# 3_-_Fuses.net
KiCad netlist of a schematic drawn in Altium Designer
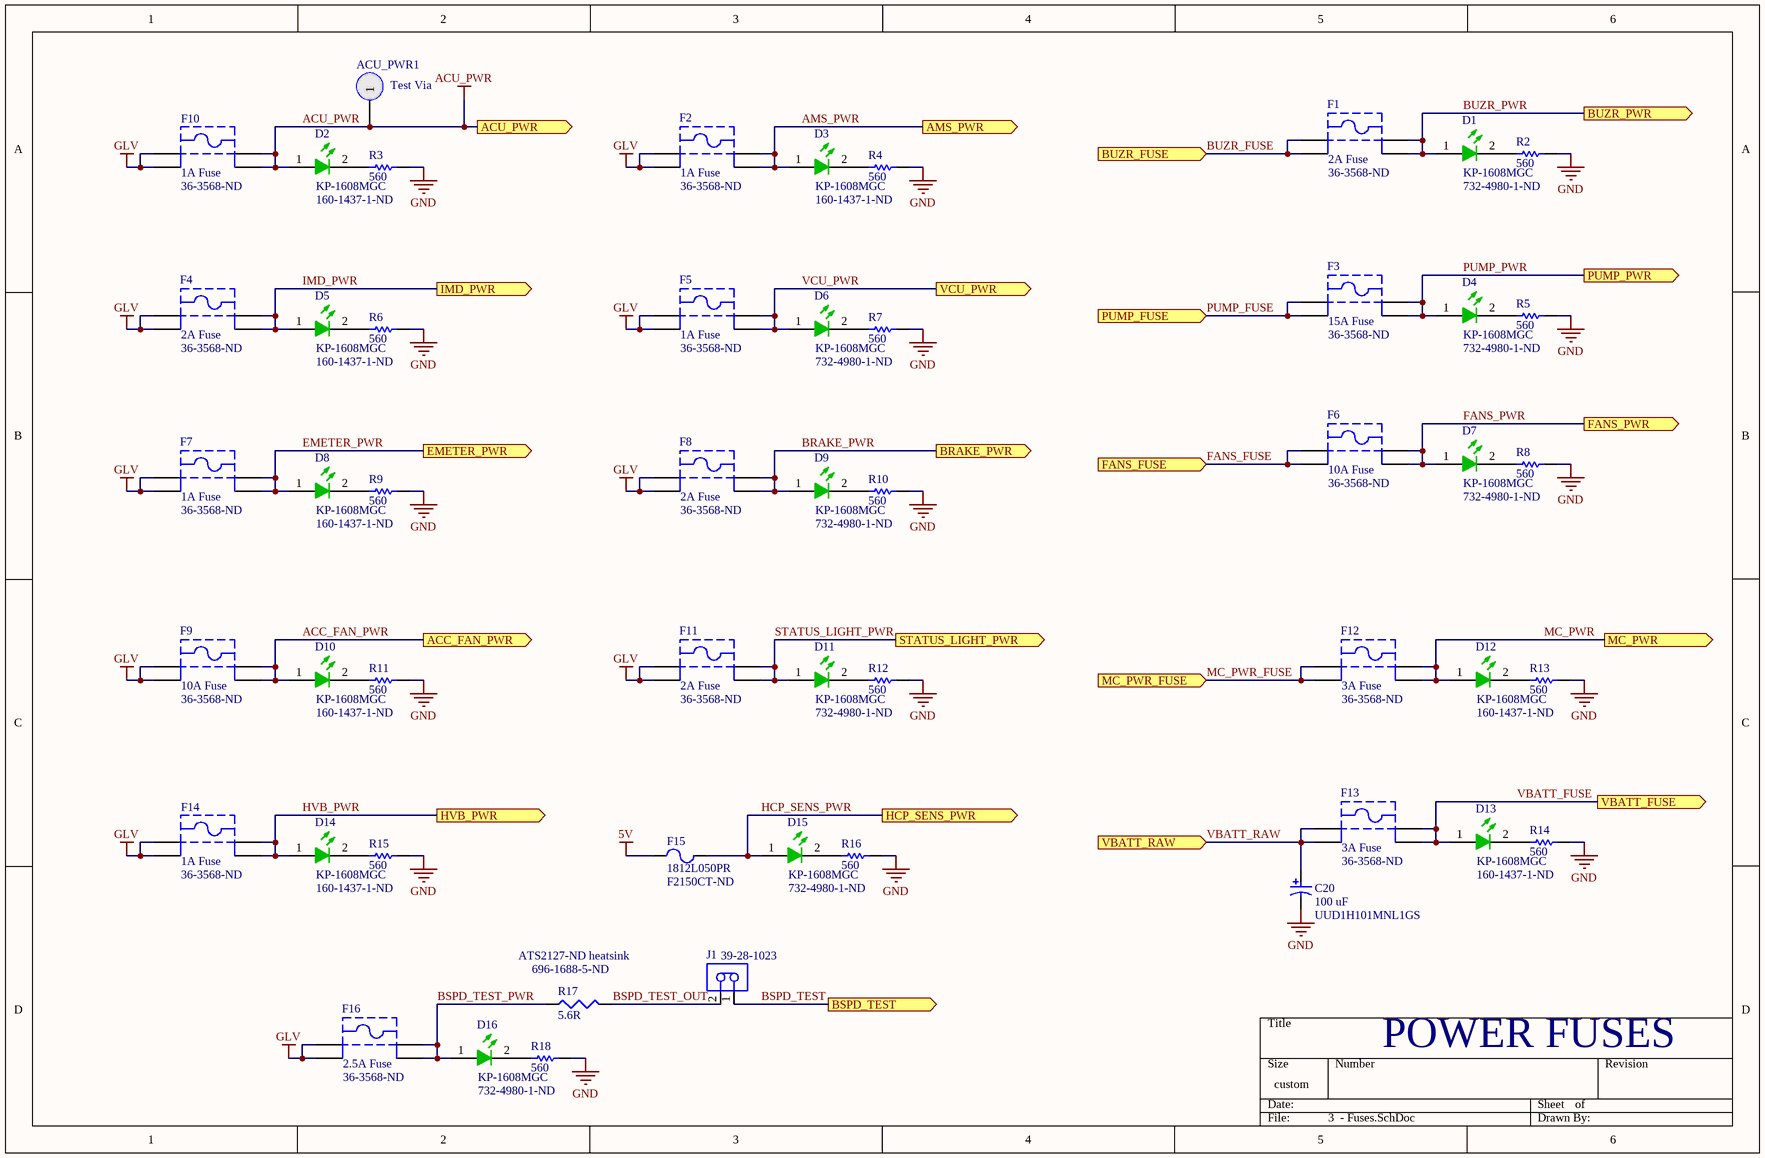
[diagram p0: 3  - Fuses.SchDoc]

(export (version "E")
  (design (tool "Eeschema 10.0.6"))
  (components
    (comp (ref "ACU_PWR1")
      (value "Test Via")
      (footprint "Test Via")
      (libsource (lib "BRAKETEMPComponents") (part "Test VIa"))
    )
    (comp (ref "C20")
      (value "UUD1H101MNL1GS")
      (footprint "NIC-CAPA2-8X10_V")
      (fields
        (field (name "MANUFACTURER") "Nichicon")
        (field (name "RATED CAPACITANCE") "100 uF")
        (field (name "TOLERANCE") "±20%")
      )
      (libsource (lib "Altium Content Vault") (part "CMP-0687-00073-1"))
    )
    (comp (ref "D1")
      (value "KP-1608MGC")
      (footprint "KING-0603LED_GREEN_V")
      (description "LED, SMT, 0603(1608), 1.1mm thickness, Green")
      (fields
        (field (name "MANUFACTURER") "Kingbright")
        (field (name "SUPPLIER PART NUMBER 1") "732-4980-1-ND")
      )
      (libsource (lib "Altium Content Vault") (part "KING-LED-GREEN-A1K2-2"))
    )
    (comp (ref "D2")
      (value "KP-1608MGC")
      (footprint "KING-0603LED_GREEN_V")
      (description "LED, SMT, 0603(1608), 1.1mm thickness, Green")
      (fields
        (field (name "MANUFACTURER") "Kingbright")
        (field (name "SUPPLIER PART NUMBER 1") "160-1437-1-ND")
      )
      (libsource (lib "Altium Content Vault") (part "KING-LED-GREEN-A1K2-2"))
    )
    (comp (ref "D3")
      (value "KP-1608MGC")
      (footprint "KING-0603LED_GREEN_V")
      (description "LED, SMT, 0603(1608), 1.1mm thickness, Green")
      (fields
        (field (name "MANUFACTURER") "Kingbright")
        (field (name "SUPPLIER PART NUMBER 1") "160-1437-1-ND")
      )
      (libsource (lib "Altium Content Vault") (part "KING-LED-GREEN-A1K2-2"))
    )
    (comp (ref "D4")
      (value "KP-1608MGC")
      (footprint "KING-0603LED_GREEN_V")
      (description "LED, SMT, 0603(1608), 1.1mm thickness, Green")
      (fields
        (field (name "MANUFACTURER") "Kingbright")
        (field (name "SUPPLIER PART NUMBER 1") "732-4980-1-ND")
      )
      (libsource (lib "Altium Content Vault") (part "KING-LED-GREEN-A1K2-2"))
    )
    (comp (ref "D5")
      (value "KP-1608MGC")
      (footprint "KING-0603LED_GREEN_V")
      (description "LED, SMT, 0603(1608), 1.1mm thickness, Green")
      (fields
        (field (name "MANUFACTURER") "Kingbright")
        (field (name "SUPPLIER PART NUMBER 1") "160-1437-1-ND")
      )
      (libsource (lib "Altium Content Vault") (part "KING-LED-GREEN-A1K2-2"))
    )
    (comp (ref "D6")
      (value "KP-1608MGC")
      (footprint "KING-0603LED_GREEN_V")
      (description "LED, SMT, 0603(1608), 1.1mm thickness, Green")
      (fields
        (field (name "MANUFACTURER") "Kingbright")
        (field (name "SUPPLIER PART NUMBER 1") "732-4980-1-ND")
      )
      (libsource (lib "Altium Content Vault") (part "KING-LED-GREEN-A1K2-2"))
    )
    (comp (ref "D7")
      (value "KP-1608MGC")
      (footprint "KING-0603LED_GREEN_V")
      (description "LED, SMT, 0603(1608), 1.1mm thickness, Green")
      (fields
        (field (name "MANUFACTURER") "Kingbright")
        (field (name "SUPPLIER PART NUMBER 1") "732-4980-1-ND")
      )
      (libsource (lib "Altium Content Vault") (part "KING-LED-GREEN-A1K2-2"))
    )
    (comp (ref "D8")
      (value "KP-1608MGC")
      (footprint "KING-0603LED_GREEN_V")
      (description "LED, SMT, 0603(1608), 1.1mm thickness, Green")
      (fields
        (field (name "MANUFACTURER") "Kingbright")
        (field (name "SUPPLIER PART NUMBER 1") "160-1437-1-ND")
      )
      (libsource (lib "Altium Content Vault") (part "KING-LED-GREEN-A1K2-2"))
    )
    (comp (ref "D9")
      (value "KP-1608MGC")
      (footprint "KING-0603LED_GREEN_V")
      (description "LED, SMT, 0603(1608), 1.1mm thickness, Green")
      (fields
        (field (name "MANUFACTURER") "Kingbright")
        (field (name "SUPPLIER PART NUMBER 1") "732-4980-1-ND")
      )
      (libsource (lib "Altium Content Vault") (part "KING-LED-GREEN-A1K2-2"))
    )
    (comp (ref "D10")
      (value "KP-1608MGC")
      (footprint "KING-0603LED_GREEN_V")
      (description "LED, SMT, 0603(1608), 1.1mm thickness, Green")
      (fields
        (field (name "MANUFACTURER") "Kingbright")
        (field (name "SUPPLIER PART NUMBER 1") "160-1437-1-ND")
      )
      (libsource (lib "Altium Content Vault") (part "KING-LED-GREEN-A1K2-2"))
    )
    (comp (ref "D11")
      (value "KP-1608MGC")
      (footprint "KING-0603LED_GREEN_V")
      (description "LED, SMT, 0603(1608), 1.1mm thickness, Green")
      (fields
        (field (name "MANUFACTURER") "Kingbright")
        (field (name "SUPPLIER PART NUMBER 1") "732-4980-1-ND")
      )
      (libsource (lib "Altium Content Vault") (part "KING-LED-GREEN-A1K2-2"))
    )
    (comp (ref "D12")
      (value "KP-1608MGC")
      (footprint "KING-0603LED_GREEN_V")
      (description "LED, SMT, 0603(1608), 1.1mm thickness, Green")
      (fields
        (field (name "MANUFACTURER") "Kingbright")
        (field (name "SUPPLIER PART NUMBER 1") "160-1437-1-ND")
      )
      (libsource (lib "Altium Content Vault") (part "KING-LED-GREEN-A1K2-2"))
    )
    (comp (ref "D13")
      (value "KP-1608MGC")
      (footprint "KING-0603LED_GREEN_V")
      (description "LED, SMT, 0603(1608), 1.1mm thickness, Green")
      (fields
        (field (name "MANUFACTURER") "Kingbright")
        (field (name "SUPPLIER PART NUMBER 1") "160-1437-1-ND")
      )
      (libsource (lib "Altium Content Vault") (part "KING-LED-GREEN-A1K2-2"))
    )
    (comp (ref "D14")
      (value "KP-1608MGC")
      (footprint "KING-0603LED_GREEN_V")
      (description "LED, SMT, 0603(1608), 1.1mm thickness, Green")
      (fields
        (field (name "MANUFACTURER") "Kingbright")
        (field (name "SUPPLIER PART NUMBER 1") "160-1437-1-ND")
      )
      (libsource (lib "Altium Content Vault") (part "KING-LED-GREEN-A1K2-2"))
    )
    (comp (ref "D15")
      (value "KP-1608MGC")
      (footprint "KING-0603LED_GREEN_V")
      (description "LED, SMT, 0603(1608), 1.1mm thickness, Green")
      (fields
        (field (name "MANUFACTURER") "Kingbright")
        (field (name "SUPPLIER PART NUMBER 1") "732-4980-1-ND")
      )
      (libsource (lib "Altium Content Vault") (part "KING-LED-GREEN-A1K2-2"))
    )
    (comp (ref "D16")
      (value "KP-1608MGC")
      (footprint "KING-0603LED_GREEN_V")
      (description "LED, SMT, 0603(1608), 1.1mm thickness, Green")
      (fields
        (field (name "MANUFACTURER") "Kingbright")
        (field (name "SUPPLIER PART NUMBER 1") "732-4980-1-ND")
      )
      (libsource (lib "Altium Content Vault") (part "KING-LED-GREEN-A1K2-2"))
    )
    (comp (ref "F1")
      (value "36-3568-ND")
      (footprint "KSTN-3568_V")
      (description "Fuse Holder, 20 A, 500 V, -50 to 145 degC, 4-Pin THD, RoHS")
      (fields (field (name "MANUFACTURER") "Keystone"))
      (libsource (lib "Altium Content Vault") (part "FUSE_HOLDER-4"))
    )
    (comp (ref "F2")
      (value "36-3568-ND")
      (footprint "KSTN-3568_V")
      (description "Fuse Holder, 20 A, 500 V, -50 to 145 degC, 4-Pin THD, RoHS")
      (fields (field (name "MANUFACTURER") "Keystone"))
      (libsource (lib "Altium Content Vault") (part "FUSE_HOLDER-4"))
    )
    (comp (ref "F3")
      (value "36-3568-ND")
      (footprint "KSTN-3568_V")
      (description "Fuse Holder, 20 A, 500 V, -50 to 145 degC, 4-Pin THD, RoHS")
      (fields (field (name "MANUFACTURER") "Keystone"))
      (libsource (lib "Altium Content Vault") (part "FUSE_HOLDER-4"))
    )
    (comp (ref "F4")
      (value "36-3568-ND")
      (footprint "KSTN-3568_V")
      (description "Fuse Holder, 20 A, 500 V, -50 to 145 degC, 4-Pin THD, RoHS")
      (fields (field (name "MANUFACTURER") "Keystone"))
      (libsource (lib "Altium Content Vault") (part "FUSE_HOLDER-4"))
    )
    (comp (ref "F5")
      (value "36-3568-ND")
      (footprint "KSTN-3568_V")
      (description "Fuse Holder, 20 A, 500 V, -50 to 145 degC, 4-Pin THD, RoHS")
      (fields (field (name "MANUFACTURER") "Keystone"))
      (libsource (lib "Altium Content Vault") (part "FUSE_HOLDER-4"))
    )
    (comp (ref "F6")
      (value "36-3568-ND")
      (footprint "KSTN-3568_V")
      (fields (field (name "MANUFACTURER") "Keystone"))
      (libsource (lib "Altium Content Vault") (part "FUSE_HOLDER-4"))
    )
    (comp (ref "F7")
      (value "36-3568-ND")
      (footprint "KSTN-3568_V")
      (description "Fuse Holder, 20 A, 500 V, -50 to 145 degC, 4-Pin THD, RoHS")
      (fields (field (name "MANUFACTURER") "Keystone"))
      (libsource (lib "Altium Content Vault") (part "FUSE_HOLDER-4"))
    )
    (comp (ref "F8")
      (value "36-3568-ND")
      (footprint "KSTN-3568_V")
      (description "Fuse Holder, 20 A, 500 V, -50 to 145 degC, 4-Pin THD, RoHS")
      (fields (field (name "MANUFACTURER") "Keystone"))
      (libsource (lib "Altium Content Vault") (part "FUSE_HOLDER-4"))
    )
    (comp (ref "F9")
      (value "36-3568-ND")
      (footprint "KSTN-3568_V")
      (description "Fuse Holder, 20 A, 500 V, -50 to 145 degC, 4-Pin THD, RoHS")
      (fields (field (name "MANUFACTURER") "Keystone"))
      (libsource (lib "Altium Content Vault") (part "FUSE_HOLDER-4"))
    )
    (comp (ref "F10")
      (value "36-3568-ND")
      (footprint "KSTN-3568_V")
      (description "Fuse Holder, 20 A, 500 V, -50 to 145 degC, 4-Pin THD, RoHS")
      (fields (field (name "MANUFACTURER") "Keystone"))
      (libsource (lib "Altium Content Vault") (part "FUSE_HOLDER-4"))
    )
    (comp (ref "F11")
      (value "36-3568-ND")
      (footprint "KSTN-3568_V")
      (description "Fuse Holder, 20 A, 500 V, -50 to 145 degC, 4-Pin THD, RoHS")
      (fields (field (name "MANUFACTURER") "Keystone"))
      (libsource (lib "Altium Content Vault") (part "FUSE_HOLDER-4"))
    )
    (comp (ref "F12")
      (value "36-3568-ND")
      (footprint "KSTN-3568_V")
      (description "Fuse Holder, 20 A, 500 V, -50 to 145 degC, 4-Pin THD, RoHS")
      (fields (field (name "MANUFACTURER") "Keystone"))
      (libsource (lib "Altium Content Vault") (part "FUSE_HOLDER-4"))
    )
    (comp (ref "F13")
      (value "36-3568-ND")
      (footprint "KSTN-3568_V")
      (description "Fuse Holder, 20 A, 500 V, -50 to 145 degC, 4-Pin THD, RoHS")
      (fields (field (name "MANUFACTURER") "Keystone"))
      (libsource (lib "Altium Content Vault") (part "FUSE_HOLDER-4"))
    )
    (comp (ref "F14")
      (value "36-3568-ND")
      (footprint "KSTN-3568_V")
      (description "Fuse Holder, 20 A, 500 V, -50 to 145 degC, 4-Pin THD, RoHS")
      (fields (field (name "MANUFACTURER") "Keystone"))
      (libsource (lib "Altium Content Vault") (part "FUSE_HOLDER-4"))
    )
    (comp (ref "F15")
      (value "1812L050PR")
      (footprint "LFUS-1812L050_V")
      (fields (field (name "TOLERANCE") "1%") (field (name "SUPPLIER PART NUMBER 1") "F2150CT-ND"))
      (libsource (lib "Power_PCB") (part "CMP-1700-00002-1"))
    )
    (comp (ref "F16")
      (value "36-3568-ND")
      (footprint "KSTN-3568_V")
      (description "Fuse Holder, 20 A, 500 V, -50 to 145 degC, 4-Pin THD, RoHS")
      (fields (field (name "MANUFACTURER") "Keystone"))
      (libsource (lib "Altium Content Vault") (part "FUSE_HOLDER-4"))
    )
    (comp (ref "J1")
      (value "39-28-1023")
      (footprint "MOLX-39-28-1023-2_V")
      (fields (field (name "MANUFACTURER") "Molex"))
      (libsource (lib "Altium Content Vault") (part "CN-2P-F-QF2"))
    )
    (comp (ref "R2")
      (value "560")
      (footprint "RESC0603(1608)_L")
      (description "0603 (1608 Metric) Chip Resistor")
      (libsource (lib "Altium Content Vault") (part "RES_3"))
    )
    (comp (ref "R3")
      (value "560")
      (footprint "RESC0603(1608)_L")
      (description "0603 (1608 Metric) Chip Resistor")
      (libsource (lib "Altium Content Vault") (part "RES_3"))
    )
    (comp (ref "R4")
      (value "560")
      (footprint "RESC0603(1608)_L")
      (description "0603 (1608 Metric) Chip Resistor")
      (libsource (lib "Altium Content Vault") (part "RES_3"))
    )
    (comp (ref "R5")
      (value "560")
      (footprint "RESC0603(1608)_L")
      (description "0603 (1608 Metric) Chip Resistor")
      (libsource (lib "Altium Content Vault") (part "RES_3"))
    )
    (comp (ref "R6")
      (value "560")
      (footprint "RESC0603(1608)_L")
      (description "0603 (1608 Metric) Chip Resistor")
      (libsource (lib "Altium Content Vault") (part "RES_3"))
    )
    (comp (ref "R7")
      (value "560")
      (footprint "RESC0603(1608)_L")
      (description "0603 (1608 Metric) Chip Resistor")
      (libsource (lib "Altium Content Vault") (part "RES_3"))
    )
    (comp (ref "R8")
      (value "560")
      (footprint "RESC0603(1608)_L")
      (description "0603 (1608 Metric) Chip Resistor")
      (libsource (lib "Altium Content Vault") (part "RES_3"))
    )
    (comp (ref "R9")
      (value "560")
      (footprint "RESC0603(1608)_L")
      (description "0603 (1608 Metric) Chip Resistor")
      (libsource (lib "Altium Content Vault") (part "RES_3"))
    )
    (comp (ref "R10")
      (value "560")
      (footprint "RESC0603(1608)_L")
      (description "0603 (1608 Metric) Chip Resistor")
      (libsource (lib "Altium Content Vault") (part "RES_3"))
    )
    (comp (ref "R11")
      (value "560")
      (footprint "RESC0603(1608)_L")
      (description "0603 (1608 Metric) Chip Resistor")
      (libsource (lib "Altium Content Vault") (part "RES_3"))
    )
    (comp (ref "R12")
      (value "560")
      (footprint "RESC0603(1608)_L")
      (description "0603 (1608 Metric) Chip Resistor")
      (libsource (lib "Altium Content Vault") (part "RES_3"))
    )
    (comp (ref "R13")
      (value "560")
      (footprint "RESC0603(1608)_L")
      (description "0603 (1608 Metric) Chip Resistor")
      (libsource (lib "Altium Content Vault") (part "RES_3"))
    )
    (comp (ref "R14")
      (value "560")
      (footprint "RESC0603(1608)_L")
      (description "0603 (1608 Metric) Chip Resistor")
      (libsource (lib "Altium Content Vault") (part "RES_3"))
    )
    (comp (ref "R15")
      (value "560")
      (footprint "RESC0603(1608)_L")
      (description "0603 (1608 Metric) Chip Resistor")
      (libsource (lib "Altium Content Vault") (part "RES_3"))
    )
    (comp (ref "R16")
      (value "560")
      (footprint "RESC0603(1608)_L")
      (description "0603 (1608 Metric) Chip Resistor")
      (libsource (lib "Altium Content Vault") (part "RES_3"))
    )
    (comp (ref "R17")
      (value "5.6R")
      (footprint "TO220AC")
      (description "Resistor")
      (fields
        (field (name "SUPPLIER PART NUMBER 1") "696-1688-5-ND")
        (field (name "PUBLISHER") "Altium Limited")
      )
      (libsource (lib "Miscellaneous Devices") (part "Res3"))
    )
    (comp (ref "R18")
      (value "560")
      (footprint "RESC0603(1608)_L")
      (description "0603 (1608 Metric) Chip Resistor")
      (libsource (lib "Altium Content Vault") (part "RES_3"))
    )
  )
  (nets
    (net (code "1") (name "/ACC_FAN_PWR") (class "Default")
      (node (ref "D10") (pin "1") (pinfunction "A_1") (pintype "passive"))
      (node (ref "F9") (pin "3") (pinfunction "3_3") (pintype "passive"))
      (node (ref "F9") (pin "4") (pinfunction "4_4") (pintype "passive"))
    )
    (net (code "2") (name "/AMS_PWR") (class "Default")
      (node (ref "D3") (pin "1") (pinfunction "A_1") (pintype "passive"))
      (node (ref "F2") (pin "3") (pinfunction "3_3") (pintype "passive"))
      (node (ref "F2") (pin "4") (pinfunction "4_4") (pintype "passive"))
    )
    (net (code "3") (name "/BRAKE_PWR") (class "Default")
      (node (ref "D9") (pin "1") (pinfunction "A_1") (pintype "passive"))
      (node (ref "F8") (pin "3") (pinfunction "3_3") (pintype "passive"))
      (node (ref "F8") (pin "4") (pinfunction "4_4") (pintype "passive"))
    )
    (net (code "4") (name "/BSPD_TEST") (class "Default")
      (node (ref "J1") (pin "1") (pinfunction "1_1") (pintype "passive"))
    )
    (net (code "5") (name "/BSPD_TEST_OUT") (class "Default")
      (node (ref "J1") (pin "2") (pinfunction "2_2") (pintype "passive"))
      (node (ref "R17") (pin "2") (pinfunction "2_2") (pintype "passive"))
    )
    (net (code "6") (name "/BSPD_TEST_PWR") (class "Default")
      (node (ref "D16") (pin "1") (pinfunction "A_1") (pintype "passive"))
      (node (ref "F16") (pin "3") (pinfunction "3_3") (pintype "passive"))
      (node (ref "F16") (pin "4") (pinfunction "4_4") (pintype "passive"))
      (node (ref "R17") (pin "1") (pinfunction "1_1") (pintype "passive"))
    )
    (net (code "7") (name "/BUZR_FUSE") (class "Default")
      (node (ref "F1") (pin "1") (pinfunction "1_1") (pintype "passive"))
      (node (ref "F1") (pin "2") (pinfunction "2_2") (pintype "passive"))
    )
    (net (code "8") (name "/BUZR_PWR") (class "Default")
      (node (ref "D1") (pin "1") (pinfunction "A_1") (pintype "passive"))
      (node (ref "F1") (pin "3") (pinfunction "3_3") (pintype "passive"))
      (node (ref "F1") (pin "4") (pinfunction "4_4") (pintype "passive"))
    )
    (net (code "9") (name "/EMETER_PWR") (class "Default")
      (node (ref "D8") (pin "1") (pinfunction "A_1") (pintype "passive"))
      (node (ref "F7") (pin "3") (pinfunction "3_3") (pintype "passive"))
      (node (ref "F7") (pin "4") (pinfunction "4_4") (pintype "passive"))
    )
    (net (code "10") (name "/FANS_FUSE") (class "Default")
      (node (ref "F6") (pin "1") (pinfunction "1_1") (pintype "passive"))
      (node (ref "F6") (pin "2") (pinfunction "2_2") (pintype "passive"))
    )
    (net (code "11") (name "/FANS_PWR") (class "Default")
      (node (ref "D7") (pin "1") (pinfunction "A_1") (pintype "passive"))
      (node (ref "F6") (pin "3") (pinfunction "3_3") (pintype "passive"))
      (node (ref "F6") (pin "4") (pinfunction "4_4") (pintype "passive"))
    )
    (net (code "12") (name "/HCP_SENS_PWR") (class "Default")
      (node (ref "D15") (pin "1") (pinfunction "A_1") (pintype "passive"))
      (node (ref "F15") (pin "2") (pinfunction "2_2") (pintype "passive"))
    )
    (net (code "13") (name "/HVB_PWR") (class "Default")
      (node (ref "D14") (pin "1") (pinfunction "A_1") (pintype "passive"))
      (node (ref "F14") (pin "3") (pinfunction "3_3") (pintype "passive"))
      (node (ref "F14") (pin "4") (pinfunction "4_4") (pintype "passive"))
    )
    (net (code "14") (name "/IMD_PWR") (class "Default")
      (node (ref "D5") (pin "1") (pinfunction "A_1") (pintype "passive"))
      (node (ref "F4") (pin "3") (pinfunction "3_3") (pintype "passive"))
      (node (ref "F4") (pin "4") (pinfunction "4_4") (pintype "passive"))
    )
    (net (code "15") (name "/MC_PWR") (class "Default")
      (node (ref "D12") (pin "1") (pinfunction "A_1") (pintype "passive"))
      (node (ref "F12") (pin "3") (pinfunction "3_3") (pintype "passive"))
      (node (ref "F12") (pin "4") (pinfunction "4_4") (pintype "passive"))
    )
    (net (code "16") (name "/MC_PWR_FUSE") (class "Default")
      (node (ref "F12") (pin "1") (pinfunction "1_1") (pintype "passive"))
      (node (ref "F12") (pin "2") (pinfunction "2_2") (pintype "passive"))
    )
    (net (code "17") (name "/PUMP_FUSE") (class "Default")
      (node (ref "F3") (pin "1") (pinfunction "1_1") (pintype "passive"))
      (node (ref "F3") (pin "2") (pinfunction "2_2") (pintype "passive"))
    )
    (net (code "18") (name "/PUMP_PWR") (class "Default")
      (node (ref "D4") (pin "1") (pinfunction "A_1") (pintype "passive"))
      (node (ref "F3") (pin "3") (pinfunction "3_3") (pintype "passive"))
      (node (ref "F3") (pin "4") (pinfunction "4_4") (pintype "passive"))
    )
    (net (code "19") (name "/STATUS_LIGHT_PWR") (class "Default")
      (node (ref "D11") (pin "1") (pinfunction "A_1") (pintype "passive"))
      (node (ref "F11") (pin "3") (pinfunction "3_3") (pintype "passive"))
      (node (ref "F11") (pin "4") (pinfunction "4_4") (pintype "passive"))
    )
    (net (code "20") (name "/VBATT_FUSE") (class "Default")
      (node (ref "D13") (pin "1") (pinfunction "A_1") (pintype "passive"))
      (node (ref "F13") (pin "3") (pinfunction "3_3") (pintype "passive"))
      (node (ref "F13") (pin "4") (pinfunction "4_4") (pintype "passive"))
    )
    (net (code "21") (name "/VBATT_RAW") (class "Default")
      (node (ref "C20") (pin "1") (pinfunction "1_1") (pintype "passive"))
      (node (ref "F13") (pin "1") (pinfunction "1_1") (pintype "passive"))
      (node (ref "F13") (pin "2") (pinfunction "2_2") (pintype "passive"))
    )
    (net (code "22") (name "/VCU_PWR") (class "Default")
      (node (ref "D6") (pin "1") (pinfunction "A_1") (pintype "passive"))
      (node (ref "F5") (pin "3") (pinfunction "3_3") (pintype "passive"))
      (node (ref "F5") (pin "4") (pinfunction "4_4") (pintype "passive"))
    )
    (net (code "23") (name "5V") (class "Default")
      (node (ref "F15") (pin "1") (pinfunction "1_1") (pintype "passive"))
    )
    (net (code "24") (name "ACU_PWR") (class "Default")
      (node (ref "ACU_PWR1") (pin "1") (pinfunction "1_1") (pintype "passive"))
      (node (ref "D2") (pin "1") (pinfunction "A_1") (pintype "passive"))
      (node (ref "F10") (pin "3") (pinfunction "3_3") (pintype "passive"))
      (node (ref "F10") (pin "4") (pinfunction "4_4") (pintype "passive"))
    )
    (net (code "25") (name "GLV") (class "Default")
      (node (ref "F10") (pin "1") (pinfunction "1_1") (pintype "passive"))
      (node (ref "F10") (pin "2") (pinfunction "2_2") (pintype "passive"))
      (node (ref "F11") (pin "1") (pinfunction "1_1") (pintype "passive"))
      (node (ref "F11") (pin "2") (pinfunction "2_2") (pintype "passive"))
      (node (ref "F14") (pin "1") (pinfunction "1_1") (pintype "passive"))
      (node (ref "F14") (pin "2") (pinfunction "2_2") (pintype "passive"))
      (node (ref "F16") (pin "1") (pinfunction "1_1") (pintype "passive"))
      (node (ref "F16") (pin "2") (pinfunction "2_2") (pintype "passive"))
      (node (ref "F2") (pin "1") (pinfunction "1_1") (pintype "passive"))
      (node (ref "F2") (pin "2") (pinfunction "2_2") (pintype "passive"))
      (node (ref "F4") (pin "1") (pinfunction "1_1") (pintype "passive"))
      (node (ref "F4") (pin "2") (pinfunction "2_2") (pintype "passive"))
      (node (ref "F5") (pin "1") (pinfunction "1_1") (pintype "passive"))
      (node (ref "F5") (pin "2") (pinfunction "2_2") (pintype "passive"))
      (node (ref "F7") (pin "1") (pinfunction "1_1") (pintype "passive"))
      (node (ref "F7") (pin "2") (pinfunction "2_2") (pintype "passive"))
      (node (ref "F8") (pin "1") (pinfunction "1_1") (pintype "passive"))
      (node (ref "F8") (pin "2") (pinfunction "2_2") (pintype "passive"))
      (node (ref "F9") (pin "1") (pinfunction "1_1") (pintype "passive"))
      (node (ref "F9") (pin "2") (pinfunction "2_2") (pintype "passive"))
    )
    (net (code "26") (name "GND") (class "Default")
      (node (ref "C20") (pin "2") (pinfunction "2_2") (pintype "passive"))
      (node (ref "R10") (pin "2") (pinfunction "2_2") (pintype "passive"))
      (node (ref "R11") (pin "2") (pinfunction "2_2") (pintype "passive"))
      (node (ref "R12") (pin "2") (pinfunction "2_2") (pintype "passive"))
      (node (ref "R13") (pin "2") (pinfunction "2_2") (pintype "passive"))
      (node (ref "R14") (pin "2") (pinfunction "2_2") (pintype "passive"))
      (node (ref "R15") (pin "2") (pinfunction "2_2") (pintype "passive"))
      (node (ref "R16") (pin "2") (pinfunction "2_2") (pintype "passive"))
      (node (ref "R18") (pin "2") (pinfunction "2_2") (pintype "passive"))
      (node (ref "R2") (pin "2") (pinfunction "2_2") (pintype "passive"))
      (node (ref "R3") (pin "2") (pinfunction "2_2") (pintype "passive"))
      (node (ref "R4") (pin "2") (pinfunction "2_2") (pintype "passive"))
      (node (ref "R5") (pin "2") (pinfunction "2_2") (pintype "passive"))
      (node (ref "R6") (pin "2") (pinfunction "2_2") (pintype "passive"))
      (node (ref "R7") (pin "2") (pinfunction "2_2") (pintype "passive"))
      (node (ref "R8") (pin "2") (pinfunction "2_2") (pintype "passive"))
      (node (ref "R9") (pin "2") (pinfunction "2_2") (pintype "passive"))
    )
    (net (code "27") (name "Net-(D1-K)") (class "Default")
      (node (ref "D1") (pin "2") (pinfunction "K_2") (pintype "passive"))
      (node (ref "R2") (pin "1") (pinfunction "1_1") (pintype "passive"))
    )
    (net (code "28") (name "Net-(D2-K)") (class "Default")
      (node (ref "D2") (pin "2") (pinfunction "K_2") (pintype "passive"))
      (node (ref "R3") (pin "1") (pinfunction "1_1") (pintype "passive"))
    )
    (net (code "29") (name "Net-(D3-K)") (class "Default")
      (node (ref "D3") (pin "2") (pinfunction "K_2") (pintype "passive"))
      (node (ref "R4") (pin "1") (pinfunction "1_1") (pintype "passive"))
    )
    (net (code "30") (name "Net-(D4-K)") (class "Default")
      (node (ref "D4") (pin "2") (pinfunction "K_2") (pintype "passive"))
      (node (ref "R5") (pin "1") (pinfunction "1_1") (pintype "passive"))
    )
    (net (code "31") (name "Net-(D5-K)") (class "Default")
      (node (ref "D5") (pin "2") (pinfunction "K_2") (pintype "passive"))
      (node (ref "R6") (pin "1") (pinfunction "1_1") (pintype "passive"))
    )
    (net (code "32") (name "Net-(D6-K)") (class "Default")
      (node (ref "D6") (pin "2") (pinfunction "K_2") (pintype "passive"))
      (node (ref "R7") (pin "1") (pinfunction "1_1") (pintype "passive"))
    )
    (net (code "33") (name "Net-(D7-K)") (class "Default")
      (node (ref "D7") (pin "2") (pinfunction "K_2") (pintype "passive"))
      (node (ref "R8") (pin "1") (pinfunction "1_1") (pintype "passive"))
    )
    (net (code "34") (name "Net-(D8-K)") (class "Default")
      (node (ref "D8") (pin "2") (pinfunction "K_2") (pintype "passive"))
      (node (ref "R9") (pin "1") (pinfunction "1_1") (pintype "passive"))
    )
    (net (code "35") (name "Net-(D9-K)") (class "Default")
      (node (ref "D9") (pin "2") (pinfunction "K_2") (pintype "passive"))
      (node (ref "R10") (pin "1") (pinfunction "1_1") (pintype "passive"))
    )
    (net (code "36") (name "Net-(D10-K)") (class "Default")
      (node (ref "D10") (pin "2") (pinfunction "K_2") (pintype "passive"))
      (node (ref "R11") (pin "1") (pinfunction "1_1") (pintype "passive"))
    )
    (net (code "37") (name "Net-(D11-K)") (class "Default")
      (node (ref "D11") (pin "2") (pinfunction "K_2") (pintype "passive"))
      (node (ref "R12") (pin "1") (pinfunction "1_1") (pintype "passive"))
    )
    (net (code "38") (name "Net-(D12-K)") (class "Default")
      (node (ref "D12") (pin "2") (pinfunction "K_2") (pintype "passive"))
      (node (ref "R13") (pin "1") (pinfunction "1_1") (pintype "passive"))
    )
    (net (code "39") (name "Net-(D13-K)") (class "Default")
      (node (ref "D13") (pin "2") (pinfunction "K_2") (pintype "passive"))
      (node (ref "R14") (pin "1") (pinfunction "1_1") (pintype "passive"))
    )
    (net (code "40") (name "Net-(D14-K)") (class "Default")
      (node (ref "D14") (pin "2") (pinfunction "K_2") (pintype "passive"))
      (node (ref "R15") (pin "1") (pinfunction "1_1") (pintype "passive"))
    )
    (net (code "41") (name "Net-(D15-K)") (class "Default")
      (node (ref "D15") (pin "2") (pinfunction "K_2") (pintype "passive"))
      (node (ref "R16") (pin "1") (pinfunction "1_1") (pintype "passive"))
    )
    (net (code "42") (name "Net-(D16-K)") (class "Default")
      (node (ref "D16") (pin "2") (pinfunction "K_2") (pintype "passive"))
      (node (ref "R18") (pin "1") (pinfunction "1_1") (pintype "passive"))
    )
  )
)
